# SCH5.net
KiCad netlist of a schematic drawn in Altium Designer
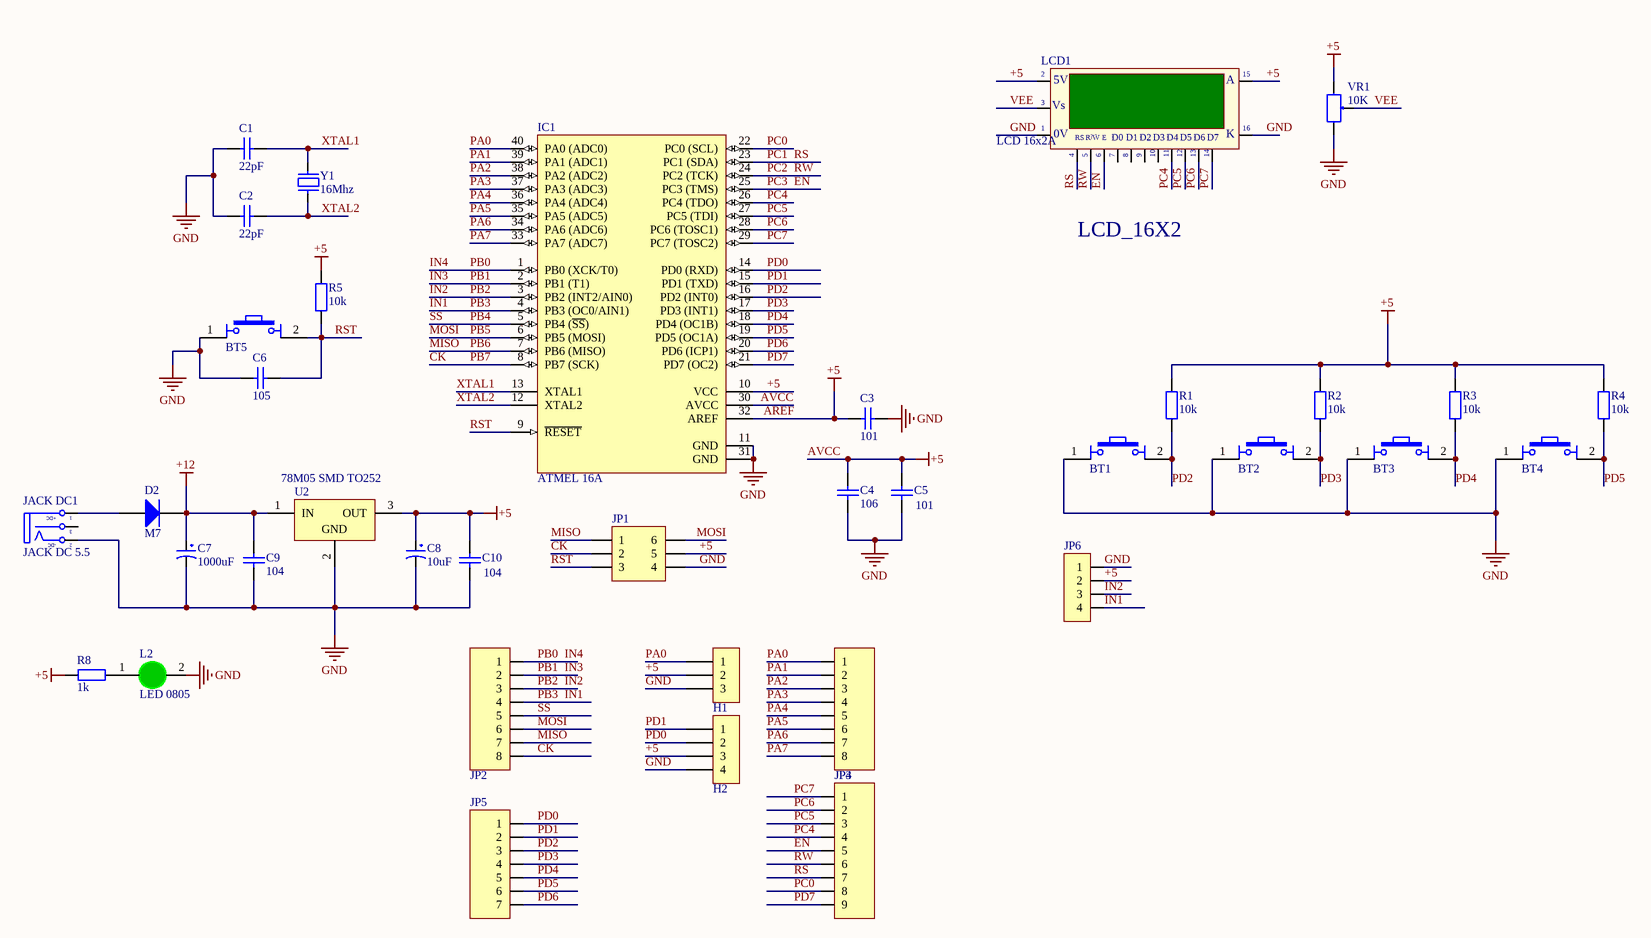
[diagram p0: SCH5.SchDoc]

(export (version "E")
  (design (tool "Eeschema 10.0.6"))
  (components
    (comp (ref "BT1")
      (value "Nut Nhan 4 Chan Cam 6x6")
      (footprint "Nut Nhan 4 Chan Cam 6x6")
      (description "Nut Nhan 4 Chan 6x6mm")
      (libsource (lib "Component") (part "Nut Nhan 4 Chan Cam 6x6"))
    )
    (comp (ref "BT2")
      (value "Nut Nhan 4 Chan Cam 6x6")
      (footprint "Nut Nhan 4 Chan Cam 6x6")
      (description "Nut Nhan 4 Chan 6x6mm")
      (libsource (lib "Component") (part "Nut Nhan 4 Chan Cam 6x6"))
    )
    (comp (ref "BT3")
      (value "Nut Nhan 4 Chan Cam 6x6")
      (footprint "Nut Nhan 4 Chan Cam 6x6")
      (description "Nut Nhan 4 Chan 6x6mm")
      (libsource (lib "Component") (part "Nut Nhan 4 Chan Cam 6x6"))
    )
    (comp (ref "BT4")
      (value "Nut Nhan 4 Chan Cam 6x6")
      (footprint "Nut Nhan 4 Chan Cam 6x6")
      (description "Nut Nhan 4 Chan 6x6mm")
      (libsource (lib "Component") (part "Nut Nhan 4 Chan Cam 6x6"))
    )
    (comp (ref "BT5")
      (value "Nut Nhan 4 Chan Cam 6x6")
      (footprint "Nut Nhan 4 Chan Cam 6x6")
      (description "Nut Nhan 4 Chan 6x6mm")
      (libsource (lib "Component") (part "Nut Nhan 4 Chan Cam 6x6"))
    )
    (comp (ref "C1")
      (value "22pF")
      (footprint "tu 0805")
      (description "Dán")
      (libsource (lib "Tu dien") (part "Tu 0805 22pF 50V 10%"))
    )
    (comp (ref "C2")
      (value "22pF")
      (footprint "tu 0805")
      (description "Dán")
      (libsource (lib "Tu dien") (part "Tu 0805 22pF 50V 10%"))
    )
    (comp (ref "C3")
      (value "101")
      (footprint "tu 0805")
      (description "Dán")
      (libsource (lib "Tu dien") (part "Tu 0805 101 50V 20%"))
    )
    (comp (ref "C4")
      (value "106")
      (footprint "tu 0805")
      (description "Dán")
      (libsource (lib "Tu dien") (part "Tu 0805 106 16V 10%"))
    )
    (comp (ref "C5")
      (value "101")
      (footprint "tu 0805")
      (description "Dán")
      (libsource (lib "Tu dien") (part "Tu 0805 101 50V 20%"))
    )
    (comp (ref "C6")
      (value "105")
      (footprint "tu 0805")
      (description "Dán")
      (libsource (lib "Tu dien") (part "Tu 0805 105 50V 10%"))
    )
    (comp (ref "C7")
      (value "1000uF")
      (footprint "tu hoa 8mm")
      (description "Cắm")
      (libsource (lib "Tu dien") (part "Tu Hoa 1000uF 16V 8x20"))
    )
    (comp (ref "C8")
      (value "10uF")
      (footprint "tu hoa 4mm")
      (description "Cắm")
      (libsource (lib "Tu dien") (part "Tu Hoa 10uF 16V 4x7"))
    )
    (comp (ref "C9")
      (value "104")
      (footprint "tu 0805")
      (description "Dán")
      (libsource (lib "Tu dien") (part "Tu 0805 104 50V 10%"))
    )
    (comp (ref "C10")
      (value "104")
      (footprint "tu 0805")
      (description "Dán")
      (libsource (lib "Tu dien") (part "Tu 0805 104 50V 10%"))
    )
    (comp (ref "D2")
      (value "M7")
      (footprint "DIODE SMA")
      (description "Dán")
      (libsource (lib "Diode") (part "Diode M7 ( 4007 )"))
    )
    (comp (ref "H1")
      (value "Header 3P 2.54 Duc Thang")
      (footprint "XH2.54M-3")
      (description "Cắm")
      (libsource (lib "Header") (part "Header 3P 2.54 Duc Thang"))
    )
    (comp (ref "H2")
      (value "Header 4P 2.54 Duc Thang")
      (footprint "XH2.54M-4")
      (description "Cắm")
      (libsource (lib "Header") (part "Header 4P 2.54 Duc Thang"))
    )
    (comp (ref "IC1")
      (value "ATMEL 16A")
      (footprint "DIP40/W0.6")
      (description "8-Bit AVR Microcontroller with 16K Bytes of In-System Programmable Flash Memory")
      (libsource (lib "Thu Vien Chuan") (part "ATmega16A-PU"))
    )
    (comp (ref "JACK DC1")
      (value "JACK DC 5.5")
      (footprint "JACK DC 5.5")
      (libsource (lib "Component") (part "JACK DC 5.5"))
    )
    (comp (ref "JP1")
      (value "JP 2x3 2.54")
      (footprint "JP 2x3 DT")
      (description "Cắm")
      (libsource (lib "Jump") (part "JP 2x3 2.54 Duc Thang"))
    )
    (comp (ref "JP2")
      (value "JP 1x8 2.54")
      (footprint "JP 1x8 DT")
      (description "Cắm")
      (libsource (lib "") (part "JP 1x8 2.54 Duc Thang_1"))
    )
    (comp (ref "JP3")
      (value "JP 1x8 2.54")
      (footprint "JP 1x8 DT")
      (description "Cắm")
      (libsource (lib "Jump") (part "JP 1x8 2.54 Duc Thang"))
    )
    (comp (ref "JP4")
      (value "JP 1x9 2.54")
      (footprint "JP 1x9 DT")
      (description "Cắm")
      (libsource (lib "Jump") (part "JP 1x9 2.54 Duc Thang"))
    )
    (comp (ref "JP5")
      (value "JP 1x7 2.54")
      (footprint "JP 1x7 DT")
      (description "Cắm")
      (libsource (lib "Jump") (part "JP 1x7 2.54 Duc Thang"))
    )
    (comp (ref "JP6")
      (value "JP 1x4 2.54")
      (footprint "JP 1x4 DT")
      (description "Cắm")
      (libsource (lib "Jump") (part "JP 1x4 2.54 Duc Thang"))
    )
    (comp (ref "L2")
      (value "LED 0805")
      (footprint "LED-0805-Green")
      (description "Dán")
      (libsource (lib "Led") (part "LED 0805 Xanh La"))
    )
    (comp (ref "LCD1")
      (value "LCD 16x2A")
      (footprint "LCD16X2N")
      (description "LCD dipslay 16 char, 2 line")
      (libsource (lib "Thu Vien Chuan") (part "LCD16x2A"))
    )
    (comp (ref "R1")
      (value "10k")
      (footprint "tro smd 0805")
      (description "Dán")
      (libsource (lib "Dien Tro") (part "Tro 0805 1% 10k"))
    )
    (comp (ref "R2")
      (value "10k")
      (footprint "tro smd 0805")
      (description "Dán")
      (libsource (lib "Dien Tro") (part "Tro 0805 1% 10k"))
    )
    (comp (ref "R3")
      (value "10k")
      (footprint "tro smd 0805")
      (description "Dán")
      (libsource (lib "Dien Tro") (part "Tro 0805 1% 10k"))
    )
    (comp (ref "R4")
      (value "10k")
      (footprint "tro smd 0805")
      (description "Dán")
      (libsource (lib "Dien Tro") (part "Tro 0805 1% 10k"))
    )
    (comp (ref "R5")
      (value "10k")
      (footprint "tro smd 0805")
      (description "Dán")
      (libsource (lib "Dien Tro") (part "Tro 0805 1% 10k"))
    )
    (comp (ref "R8")
      (value "1k")
      (footprint "tro smd 0805")
      (description "Dán")
      (libsource (lib "Dien Tro") (part "Tro 0805 1% 1k"))
    )
    (comp (ref "U2")
      (value "78M05 SMD TO252")
      (footprint "TO252")
      (description "Dán")
      (libsource (lib "IC") (part "78M05 SMD TO252"))
    )
    (comp (ref "VR1")
      (value "10K")
      (footprint "Bien Tro Vi Chinh Dung")
      (description "Cắm")
      (libsource (lib "Dien Tro") (part "Bien Tro Tinh Chinh 1K Dung"))
    )
    (comp (ref "Y1")
      (value "16Mhz")
      (footprint "Thach Anh 2 chan cam")
      (description "Crystal For all Crystal 2pin.")
      (libsource (lib "Component") (part "Thach Anh 2 chan Cam"))
    )
  )
  (nets
    (net (code "1") (name "+5") (class "Default")
      (node (ref "C10") (pin "1") (pinfunction "1_1") (pintype "passive"))
      (node (ref "C3") (pin "1") (pinfunction "1_1") (pintype "passive"))
      (node (ref "C4") (pin "2") (pinfunction "2_2") (pintype "passive"))
      (node (ref "C5") (pin "1") (pinfunction "1_1") (pintype "passive"))
      (node (ref "C8") (pin "1") (pinfunction "1_1") (pintype "passive"))
      (node (ref "H1") (pin "2") (pinfunction "2_2") (pintype "passive"))
      (node (ref "H2") (pin "3") (pinfunction "3_3") (pintype "passive"))
      (node (ref "IC1") (pin "10") (pinfunction "VCC_10") (pintype "power_in"))
      (node (ref "IC1") (pin "30") (pinfunction "AVCC_30") (pintype "power_in"))
      (node (ref "IC1") (pin "32") (pinfunction "AREF_32") (pintype "power_in"))
      (node (ref "JP1") (pin "5") (pinfunction "5_5") (pintype "passive"))
      (node (ref "JP6") (pin "2") (pinfunction "2_2") (pintype "passive"))
      (node (ref "LCD1") (pin "15") (pinfunction "A_15") (pintype "passive"))
      (node (ref "LCD1") (pin "2") (pinfunction "VDD_2") (pintype "passive"))
      (node (ref "R1") (pin "2") (pinfunction "2_2") (pintype "passive"))
      (node (ref "R2") (pin "2") (pinfunction "2_2") (pintype "passive"))
      (node (ref "R3") (pin "2") (pinfunction "2_2") (pintype "passive"))
      (node (ref "R4") (pin "2") (pinfunction "2_2") (pintype "passive"))
      (node (ref "R5") (pin "2") (pinfunction "2_2") (pintype "passive"))
      (node (ref "R8") (pin "2") (pinfunction "2_2") (pintype "passive"))
      (node (ref "U2") (pin "3") (pinfunction "OUT_3") (pintype "power_in"))
      (node (ref "VR1") (pin "1") (pinfunction "1_1") (pintype "passive"))
    )
    (net (code "2") (name "+12") (class "Default")
      (node (ref "C7") (pin "1") (pinfunction "1_1") (pintype "passive"))
      (node (ref "C9") (pin "1") (pinfunction "1_1") (pintype "passive"))
      (node (ref "D2") (pin "2") (pinfunction "K_2") (pintype "passive"))
      (node (ref "U2") (pin "1") (pinfunction "IN_1") (pintype "power_in"))
    )
    (net (code "3") (name "/CK") (class "Default")
      (node (ref "IC1") (pin "8") (pinfunction "PB7_(SCK)_8") (pintype "bidirectional"))
      (node (ref "JP1") (pin "2") (pinfunction "2_2") (pintype "passive"))
      (node (ref "JP2") (pin "8") (pinfunction "8_8") (pintype "passive"))
    )
    (net (code "4") (name "/EN") (class "Default")
      (node (ref "IC1") (pin "25") (pinfunction "PC3_(TMS)_25") (pintype "bidirectional"))
      (node (ref "JP4") (pin "5") (pinfunction "5_5") (pintype "passive"))
      (node (ref "LCD1") (pin "6") (pinfunction "~{EN}_6") (pintype "passive"))
    )
    (net (code "5") (name "/IN1") (class "Default")
      (node (ref "IC1") (pin "4") (pinfunction "PB3_(OC0/AIN1)_4") (pintype "bidirectional"))
      (node (ref "JP2") (pin "4") (pinfunction "4_4") (pintype "passive"))
      (node (ref "JP6") (pin "4") (pinfunction "4_4") (pintype "passive"))
    )
    (net (code "6") (name "/IN2") (class "Default")
      (node (ref "IC1") (pin "3") (pinfunction "PB2_(INT2/AIN0)_3") (pintype "bidirectional"))
      (node (ref "JP2") (pin "3") (pinfunction "3_3") (pintype "passive"))
      (node (ref "JP6") (pin "3") (pinfunction "3_3") (pintype "passive"))
    )
    (net (code "7") (name "/IN3") (class "Default")
      (node (ref "IC1") (pin "2") (pinfunction "PB1_(T1)_2") (pintype "bidirectional"))
      (node (ref "JP2") (pin "2") (pinfunction "2_2") (pintype "passive"))
    )
    (net (code "8") (name "/IN4") (class "Default")
      (node (ref "IC1") (pin "1") (pinfunction "PB0_(XCK/T0)_1") (pintype "bidirectional"))
      (node (ref "JP2") (pin "1") (pinfunction "1_1") (pintype "passive"))
    )
    (net (code "9") (name "/MISO") (class "Default")
      (node (ref "IC1") (pin "7") (pinfunction "PB6_(MISO)_7") (pintype "bidirectional"))
      (node (ref "JP1") (pin "1") (pinfunction "1_1") (pintype "passive"))
      (node (ref "JP2") (pin "7") (pinfunction "7_7") (pintype "passive"))
    )
    (net (code "10") (name "/MOSI") (class "Default")
      (node (ref "IC1") (pin "6") (pinfunction "PB5_(MOSI)_6") (pintype "bidirectional"))
      (node (ref "JP1") (pin "6") (pinfunction "6_6") (pintype "passive"))
      (node (ref "JP2") (pin "6") (pinfunction "6_6") (pintype "passive"))
    )
    (net (code "11") (name "/PA0") (class "Default")
      (node (ref "H1") (pin "1") (pinfunction "1_1") (pintype "passive"))
      (node (ref "IC1") (pin "40") (pinfunction "PA0_(ADC0)_40") (pintype "bidirectional"))
      (node (ref "JP3") (pin "1") (pinfunction "1_1") (pintype "passive"))
    )
    (net (code "12") (name "/PA1") (class "Default")
      (node (ref "IC1") (pin "39") (pinfunction "PA1_(ADC1)_39") (pintype "bidirectional"))
      (node (ref "JP3") (pin "2") (pinfunction "2_2") (pintype "passive"))
    )
    (net (code "13") (name "/PA2") (class "Default")
      (node (ref "IC1") (pin "38") (pinfunction "PA2_(ADC2)_38") (pintype "bidirectional"))
      (node (ref "JP3") (pin "3") (pinfunction "3_3") (pintype "passive"))
    )
    (net (code "14") (name "/PA3") (class "Default")
      (node (ref "IC1") (pin "37") (pinfunction "PA3_(ADC3)_37") (pintype "bidirectional"))
      (node (ref "JP3") (pin "4") (pinfunction "4_4") (pintype "passive"))
    )
    (net (code "15") (name "/PA4") (class "Default")
      (node (ref "IC1") (pin "36") (pinfunction "PA4_(ADC4)_36") (pintype "bidirectional"))
      (node (ref "JP3") (pin "5") (pinfunction "5_5") (pintype "passive"))
    )
    (net (code "16") (name "/PA5") (class "Default")
      (node (ref "IC1") (pin "35") (pinfunction "PA5_(ADC5)_35") (pintype "bidirectional"))
      (node (ref "JP3") (pin "6") (pinfunction "6_6") (pintype "passive"))
    )
    (net (code "17") (name "/PA6") (class "Default")
      (node (ref "IC1") (pin "34") (pinfunction "PA6_(ADC6)_34") (pintype "bidirectional"))
      (node (ref "JP3") (pin "7") (pinfunction "7_7") (pintype "passive"))
    )
    (net (code "18") (name "/PA7") (class "Default")
      (node (ref "IC1") (pin "33") (pinfunction "PA7_(ADC7)_33") (pintype "bidirectional"))
      (node (ref "JP3") (pin "8") (pinfunction "8_8") (pintype "passive"))
    )
    (net (code "19") (name "/PB4") (class "Default")
      (node (ref "IC1") (pin "5") (pinfunction "PB4_(~{SS})_5") (pintype "bidirectional"))
      (node (ref "JP2") (pin "5") (pinfunction "5_5") (pintype "passive"))
    )
    (net (code "20") (name "/PC0") (class "Default")
      (node (ref "IC1") (pin "22") (pinfunction "PC0_(SCL)_22") (pintype "bidirectional"))
      (node (ref "JP4") (pin "8") (pinfunction "8_8") (pintype "passive"))
    )
    (net (code "21") (name "/PC1") (class "Default")
      (node (ref "IC1") (pin "23") (pinfunction "PC1_(SDA)_23") (pintype "bidirectional"))
      (node (ref "JP4") (pin "7") (pinfunction "7_7") (pintype "passive"))
      (node (ref "LCD1") (pin "4") (pinfunction "RS_4") (pintype "passive"))
    )
    (net (code "22") (name "/PC2") (class "Default")
      (node (ref "IC1") (pin "24") (pinfunction "PC2_(TCK)_24") (pintype "bidirectional"))
      (node (ref "JP4") (pin "6") (pinfunction "6_6") (pintype "passive"))
      (node (ref "LCD1") (pin "5") (pinfunction "R/~{W}_5") (pintype "passive"))
    )
    (net (code "23") (name "/PC4") (class "Default")
      (node (ref "IC1") (pin "26") (pinfunction "PC4_(TDO)_26") (pintype "bidirectional"))
      (node (ref "JP4") (pin "4") (pinfunction "4_4") (pintype "passive"))
      (node (ref "LCD1") (pin "11") (pinfunction "D4_11") (pintype "passive"))
    )
    (net (code "24") (name "/PC5") (class "Default")
      (node (ref "IC1") (pin "27") (pinfunction "PC5_(TDI)_27") (pintype "bidirectional"))
      (node (ref "JP4") (pin "3") (pinfunction "3_3") (pintype "passive"))
      (node (ref "LCD1") (pin "12") (pinfunction "D5_12") (pintype "passive"))
    )
    (net (code "25") (name "/PC6") (class "Default")
      (node (ref "IC1") (pin "28") (pinfunction "PC6_(TOSC1)_28") (pintype "bidirectional"))
      (node (ref "JP4") (pin "2") (pinfunction "2_2") (pintype "passive"))
      (node (ref "LCD1") (pin "13") (pinfunction "D6_13") (pintype "passive"))
    )
    (net (code "26") (name "/PC7") (class "Default")
      (node (ref "IC1") (pin "29") (pinfunction "PC7_(TOSC2)_29") (pintype "bidirectional"))
      (node (ref "JP4") (pin "1") (pinfunction "1_1") (pintype "passive"))
      (node (ref "LCD1") (pin "14") (pinfunction "D7_14") (pintype "passive"))
    )
    (net (code "27") (name "/PD0") (class "Default")
      (node (ref "H2") (pin "2") (pinfunction "2_2") (pintype "passive"))
      (node (ref "IC1") (pin "14") (pinfunction "PD0_(RXD)_14") (pintype "bidirectional"))
      (node (ref "JP5") (pin "1") (pinfunction "1_1") (pintype "passive"))
    )
    (net (code "28") (name "/PD1") (class "Default")
      (node (ref "H2") (pin "1") (pinfunction "1_1") (pintype "passive"))
      (node (ref "IC1") (pin "15") (pinfunction "PD1_(TXD)_15") (pintype "bidirectional"))
      (node (ref "JP5") (pin "2") (pinfunction "2_2") (pintype "passive"))
    )
    (net (code "29") (name "/PD2") (class "Default")
      (node (ref "BT1") (pin "2") (pintype "passive"))
      (node (ref "IC1") (pin "16") (pinfunction "PD2_(INT0)_16") (pintype "bidirectional"))
      (node (ref "JP5") (pin "3") (pinfunction "3_3") (pintype "passive"))
      (node (ref "R1") (pin "1") (pinfunction "1_1") (pintype "passive"))
    )
    (net (code "30") (name "/PD3") (class "Default")
      (node (ref "BT2") (pin "2") (pintype "passive"))
      (node (ref "IC1") (pin "17") (pinfunction "PD3_(INT1)_17") (pintype "bidirectional"))
      (node (ref "JP5") (pin "4") (pinfunction "4_4") (pintype "passive"))
      (node (ref "R2") (pin "1") (pinfunction "1_1") (pintype "passive"))
    )
    (net (code "31") (name "/PD4") (class "Default")
      (node (ref "BT3") (pin "2") (pintype "passive"))
      (node (ref "IC1") (pin "18") (pinfunction "PD4_(OC1B)_18") (pintype "bidirectional"))
      (node (ref "JP5") (pin "5") (pinfunction "5_5") (pintype "passive"))
      (node (ref "R3") (pin "1") (pinfunction "1_1") (pintype "passive"))
    )
    (net (code "32") (name "/PD5") (class "Default")
      (node (ref "BT4") (pin "2") (pintype "passive"))
      (node (ref "IC1") (pin "19") (pinfunction "PD5_(OC1A)_19") (pintype "bidirectional"))
      (node (ref "JP5") (pin "6") (pinfunction "6_6") (pintype "passive"))
      (node (ref "R4") (pin "1") (pinfunction "1_1") (pintype "passive"))
    )
    (net (code "33") (name "/PD6") (class "Default")
      (node (ref "IC1") (pin "20") (pinfunction "PD6_(ICP1)_20") (pintype "bidirectional"))
      (node (ref "JP5") (pin "7") (pinfunction "7_7") (pintype "passive"))
    )
    (net (code "34") (name "/PD7") (class "Default")
      (node (ref "IC1") (pin "21") (pinfunction "PD7_(OC2)_21") (pintype "bidirectional"))
      (node (ref "JP4") (pin "9") (pinfunction "9_9") (pintype "passive"))
    )
    (net (code "35") (name "/RST") (class "Default")
      (node (ref "BT5") (pin "2") (pintype "passive"))
      (node (ref "C6") (pin "2") (pinfunction "2_2") (pintype "passive"))
      (node (ref "IC1") (pin "9") (pinfunction "~{RESET}_9") (pintype "input"))
      (node (ref "JP1") (pin "3") (pinfunction "3_3") (pintype "passive"))
      (node (ref "R5") (pin "1") (pinfunction "1_1") (pintype "passive"))
    )
    (net (code "36") (name "/VEE") (class "Default")
      (node (ref "LCD1") (pin "3") (pinfunction "VEE_3") (pintype "passive"))
      (node (ref "VR1") (pin "2") (pinfunction "2_2") (pintype "passive"))
    )
    (net (code "37") (name "/XTAL1") (class "Default")
      (node (ref "C1") (pin "1") (pinfunction "1_1") (pintype "passive"))
      (node (ref "IC1") (pin "13") (pinfunction "XTAL1_13") (pintype "passive"))
      (node (ref "Y1") (pin "2") (pinfunction "2_2") (pintype "passive"))
    )
    (net (code "38") (name "/XTAL2") (class "Default")
      (node (ref "C2") (pin "1") (pinfunction "1_1") (pintype "passive"))
      (node (ref "IC1") (pin "12") (pinfunction "XTAL2_12") (pintype "passive"))
      (node (ref "Y1") (pin "1") (pinfunction "1_1") (pintype "passive"))
    )
    (net (code "39") (name "GND") (class "Default")
      (node (ref "BT1") (pin "1") (pintype "passive"))
      (node (ref "BT2") (pin "1") (pintype "passive"))
      (node (ref "BT3") (pin "1") (pintype "passive"))
      (node (ref "BT4") (pin "1") (pintype "passive"))
      (node (ref "BT5") (pin "1") (pintype "passive"))
      (node (ref "C1") (pin "2") (pinfunction "2_2") (pintype "passive"))
      (node (ref "C10") (pin "2") (pinfunction "2_2") (pintype "passive"))
      (node (ref "C2") (pin "2") (pinfunction "2_2") (pintype "passive"))
      (node (ref "C3") (pin "2") (pinfunction "2_2") (pintype "passive"))
      (node (ref "C4") (pin "1") (pinfunction "1_1") (pintype "passive"))
      (node (ref "C5") (pin "2") (pinfunction "2_2") (pintype "passive"))
      (node (ref "C6") (pin "1") (pinfunction "1_1") (pintype "passive"))
      (node (ref "C7") (pin "2") (pinfunction "2_2") (pintype "passive"))
      (node (ref "C8") (pin "2") (pinfunction "2_2") (pintype "passive"))
      (node (ref "C9") (pin "2") (pinfunction "2_2") (pintype "passive"))
      (node (ref "H1") (pin "3") (pinfunction "3_3") (pintype "passive"))
      (node (ref "H2") (pin "4") (pinfunction "4_4") (pintype "passive"))
      (node (ref "IC1") (pin "11") (pinfunction "GND_11") (pintype "power_in"))
      (node (ref "IC1") (pin "31") (pinfunction "GND_31") (pintype "power_in"))
      (node (ref "JACK DC1") (pin "2") (pinfunction "TN_2") (pintype "passive"))
      (node (ref "JP1") (pin "4") (pinfunction "4_4") (pintype "passive"))
      (node (ref "JP6") (pin "1") (pinfunction "1_1") (pintype "passive"))
      (node (ref "L2") (pin "2") (pinfunction "K_2") (pintype "passive"))
      (node (ref "LCD1") (pin "1") (pinfunction "GND_1") (pintype "passive"))
      (node (ref "LCD1") (pin "16") (pinfunction "K_16") (pintype "passive"))
      (node (ref "U2") (pin "2") (pinfunction "GND_2") (pintype "power_in"))
      (node (ref "VR1") (pin "3") (pinfunction "3_3") (pintype "passive"))
    )
    (net (code "40") (name "Net-(D2-A)") (class "Default")
      (node (ref "D2") (pin "1") (pinfunction "A_1") (pintype "passive"))
      (node (ref "JACK DC1") (pin "1") (pinfunction "T_1") (pintype "passive"))
    )
    (net (code "41") (name "Net-(L2-A)") (class "Default")
      (node (ref "L2") (pin "1") (pinfunction "A_1") (pintype "passive"))
      (node (ref "R8") (pin "1") (pinfunction "1_1") (pintype "passive"))
    )
    (net (code "42") (name "unconnected-(JACK DC1-S-Pad3)") (class "Default")
      (node (ref "JACK DC1") (pin "3") (pinfunction "S_3") (pintype "power_in"))
    )
    (net (code "43") (name "unconnected-(LCD1-D0-Pad7)") (class "Default")
      (node (ref "LCD1") (pin "7") (pinfunction "D0_7") (pintype "passive"))
    )
    (net (code "44") (name "unconnected-(LCD1-D1-Pad8)") (class "Default")
      (node (ref "LCD1") (pin "8") (pinfunction "D1_8") (pintype "passive"))
    )
    (net (code "45") (name "unconnected-(LCD1-D2-Pad9)") (class "Default")
      (node (ref "LCD1") (pin "9") (pinfunction "D2_9") (pintype "passive"))
    )
    (net (code "46") (name "unconnected-(LCD1-D3-Pad10)") (class "Default")
      (node (ref "LCD1") (pin "10") (pinfunction "D3_10") (pintype "passive"))
    )
  )
)
